# IoT_Greenhouse_V1_0_A_-_Esp32.net
KiCad netlist of a schematic drawn in Altium Designer
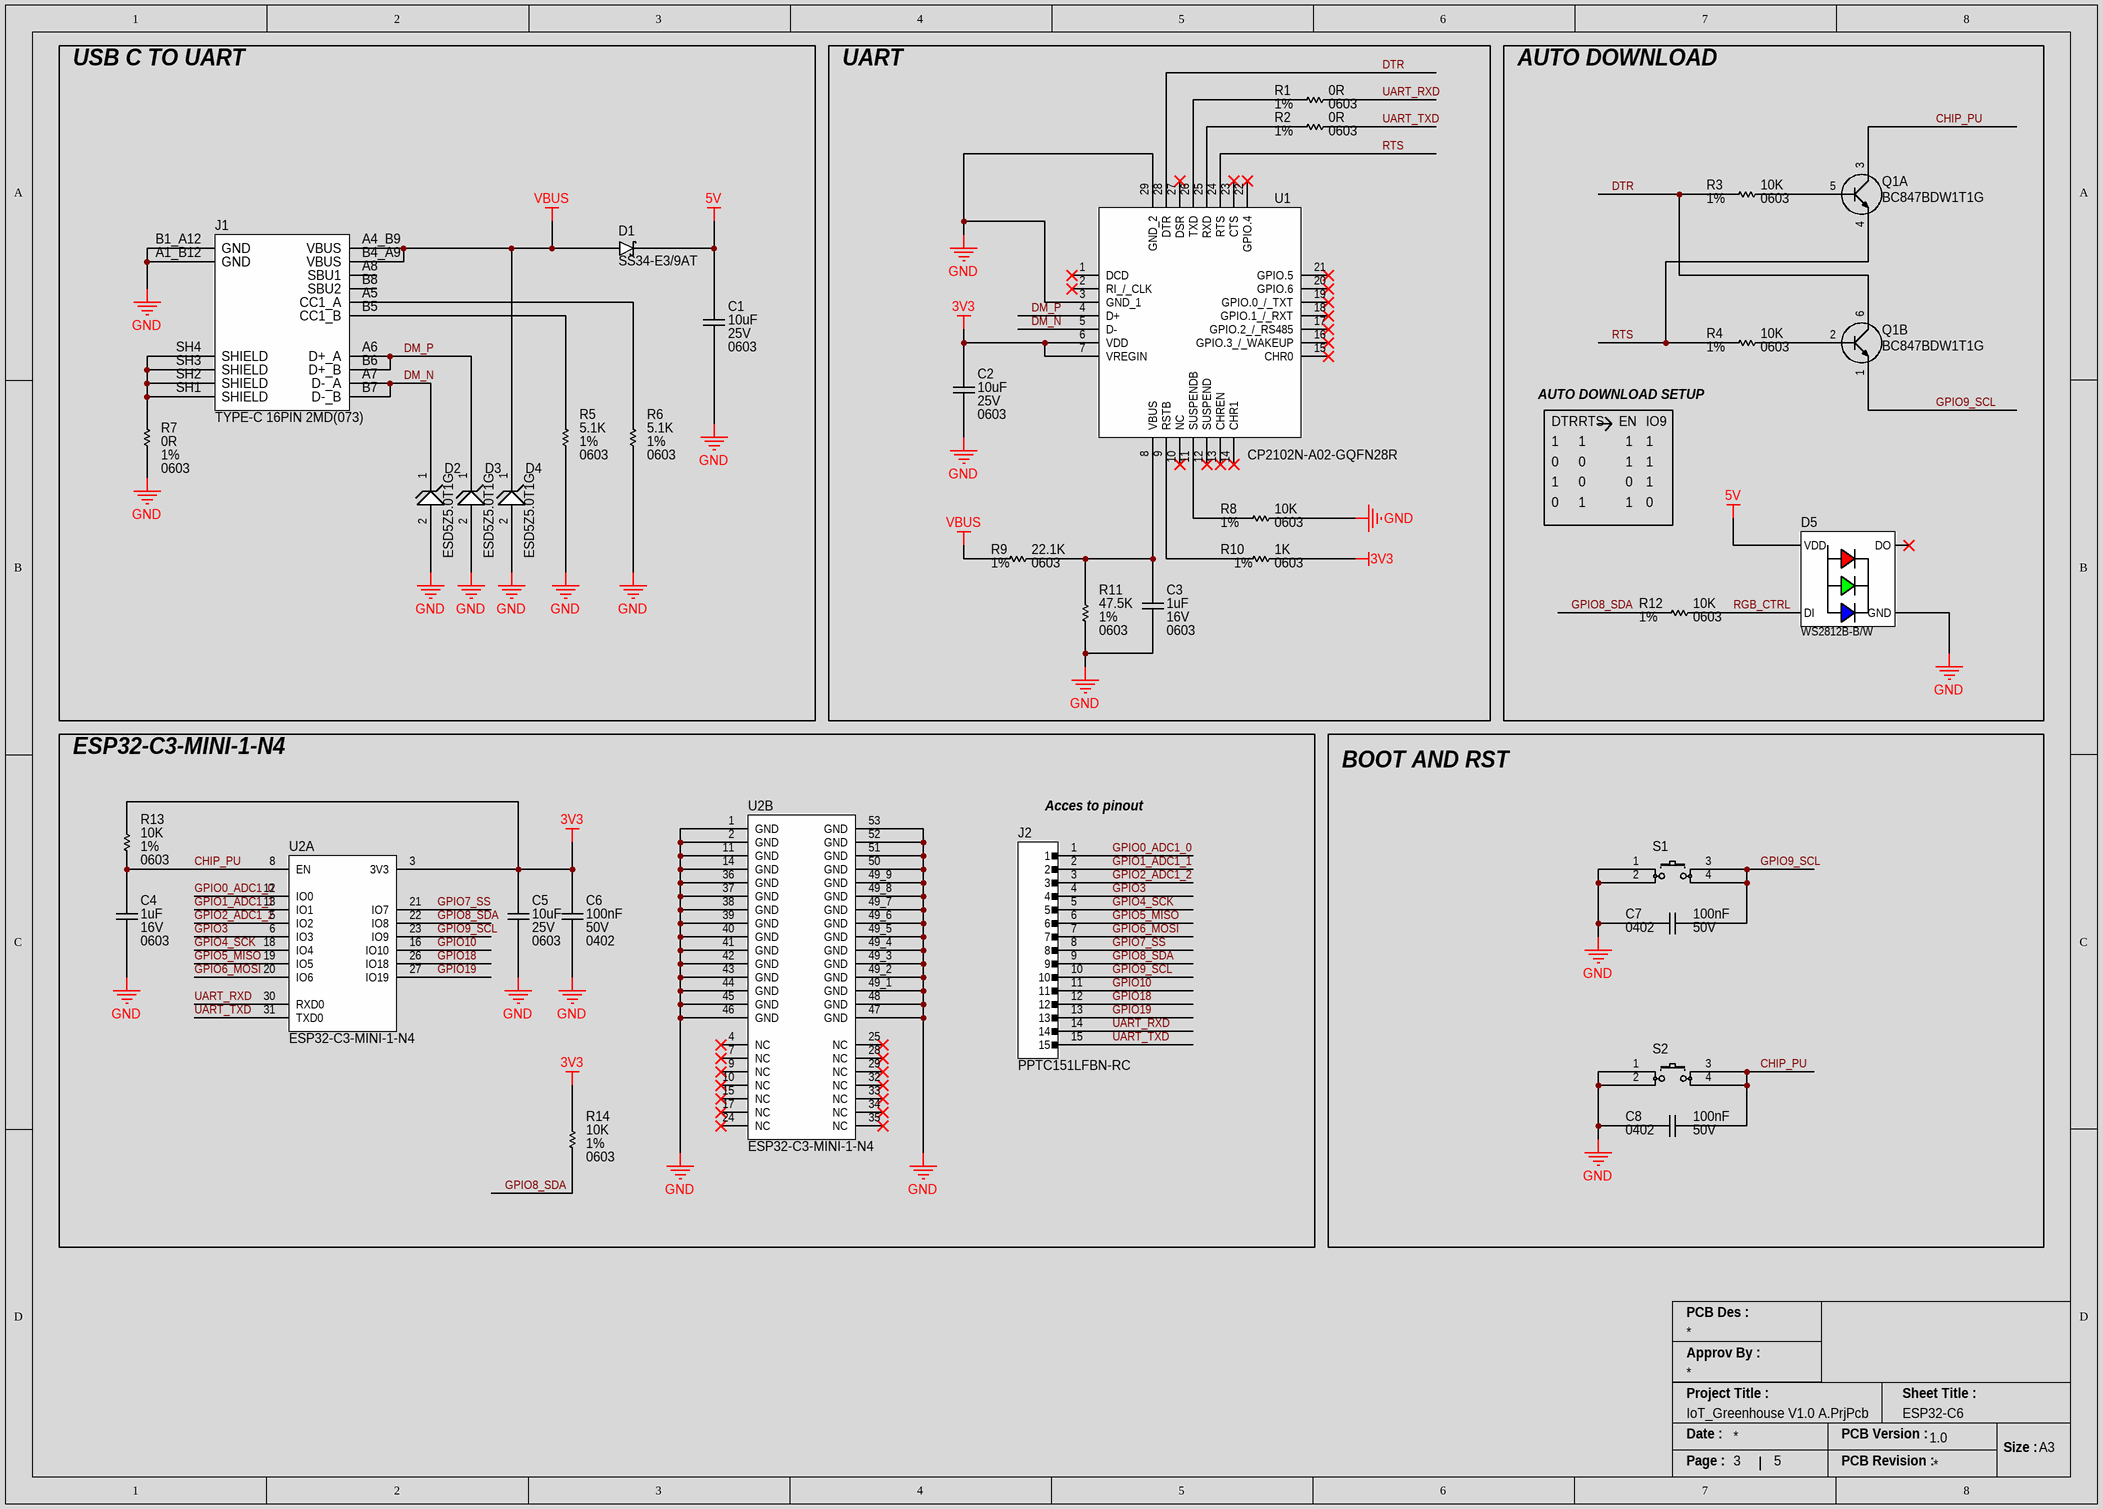
[diagram p0: IoT_Greenhouse V1.0 A - Esp32.SchDoc]

(export (version "E")
  (design (tool "Eeschema 10.0.6"))
  (components
    (comp (ref "C1")
      (value "GRM188R61E106MA73D")
      (footprint "CAP_0603_CAPC1608X08N")
      (description "Multilayer Ceramic Capacitor, 10 uF, 25 V, ± 20%, X5R, 0603 [1608 Metric]")
      (fields
        (field (name "MANUFACTURER") "Murata")
        (field (name "TOLERANCE") "20%")
        (field (name "CASE/PACKAGE") "0603")
        (field (name "CAPACITANCE") "10uF")
        (field (name "VOLTAGE RATING") "25V")
      )
      (libsource (lib "Electronic Devices_LIB") (part "CAP_10UF_25V_X5R_0603"))
    )
    (comp (ref "C2")
      (value "GRM188R61E106MA73D")
      (footprint "CAP_0603_CAPC1608X08N")
      (description "Multilayer Ceramic Capacitor, 10 uF, 25 V, ± 20%, X5R, 0603 [1608 Metric]")
      (fields
        (field (name "MANUFACTURER") "Murata")
        (field (name "TOLERANCE") "20%")
        (field (name "CASE/PACKAGE") "0603")
        (field (name "CAPACITANCE") "10uF")
        (field (name "VOLTAGE RATING") "25V")
      )
      (libsource (lib "Electronic Devices_LIB") (part "CAP_10UF_25V_X5R_0603"))
    )
    (comp (ref "C3")
      (value "CL10A105KO8NNNC")
      (footprint "CAP_0603_CAPC1608X08N")
      (description "CAP CER 1UF 16V X5R 0603")
      (fields
        (field (name "MANUFACTURER") "Samsung")
        (field (name "TOLERANCE") "10%")
        (field (name "VOLTAGE RATING") "16V")
        (field (name "CAPACITANCE") "1uF")
        (field (name "CASE/PACKAGE") "0603")
      )
      (libsource (lib "Electronic Devices_LIB") (part "CAP_1UF_16V_X5R_0603"))
    )
    (comp (ref "C4")
      (value "CL10A105KO8NNNC")
      (footprint "CAP_0603_CAPC1608X08N")
      (description "CAP CER 1UF 16V X5R 0603")
      (fields
        (field (name "MANUFACTURER") "Samsung")
        (field (name "TOLERANCE") "10%")
        (field (name "VOLTAGE RATING") "16V")
        (field (name "CAPACITANCE") "1uF")
        (field (name "CASE/PACKAGE") "0603")
      )
      (libsource (lib "Electronic Devices_LIB") (part "CAP_1UF_16V_X5R_0603"))
    )
    (comp (ref "C5")
      (value "GRM188R61E106MA73D")
      (footprint "CAP_0603_CAPC1608X08N")
      (description "Multilayer Ceramic Capacitor, 10 uF, 25 V, ± 20%, X5R, 0603 [1608 Metric]")
      (fields
        (field (name "MANUFACTURER") "Murata")
        (field (name "TOLERANCE") "20%")
        (field (name "CASE/PACKAGE") "0603")
        (field (name "CAPACITANCE") "10uF")
        (field (name "VOLTAGE RATING") "25V")
      )
      (libsource (lib "Electronic Devices_LIB") (part "CAP_10UF_25V_X5R_0603"))
    )
    (comp (ref "C6")
      (value "GRM155R71H104KE14D")
      (footprint "CAP_0402_CAPC1005X05N")
      (description "Multilayer Ceramic Capacitor, 0.1 uF, 16 V, ± 10%, X7R, 0402 [1005 Metric]")
      (fields
        (field (name "MANUFACTURER") "Murata")
        (field (name "TOLERANCE") "10%")
        (field (name "VOLTAGE RATING") "50V")
        (field (name "CAPACITANCE") "100nF")
        (field (name "CASE/PACKAGE") "0402")
      )
      (libsource (lib "Electronic Devices_LIB") (part "CAP_100NF_50V_X7R_0402"))
    )
    (comp (ref "C7")
      (value "GRM155R71H104KE14D")
      (footprint "CAP_0402_CAPC1005X05N")
      (description "Multilayer Ceramic Capacitor, 0.1 uF, 16 V, ± 10%, X7R, 0402 [1005 Metric]")
      (fields
        (field (name "MANUFACTURER") "Murata")
        (field (name "TOLERANCE") "10%")
        (field (name "VOLTAGE RATING") "50V")
        (field (name "CAPACITANCE") "100nF")
        (field (name "CASE/PACKAGE") "0402")
      )
      (libsource (lib "Electronic Devices_LIB") (part "CAP_100NF_50V_X7R_0402"))
    )
    (comp (ref "C8")
      (value "GRM155R71H104KE14D")
      (footprint "CAP_0402_CAPC1005X05N")
      (description "Multilayer Ceramic Capacitor, 0.1 uF, 16 V, ± 10%, X7R, 0402 [1005 Metric]")
      (fields
        (field (name "MANUFACTURER") "Murata")
        (field (name "TOLERANCE") "10%")
        (field (name "VOLTAGE RATING") "50V")
        (field (name "CAPACITANCE") "100nF")
        (field (name "CASE/PACKAGE") "0402")
      )
      (libsource (lib "Electronic Devices_LIB") (part "CAP_100NF_50V_X7R_0402"))
    )
    (comp (ref "D1")
      (value "SS34-E3/9AT")
      (footprint "DIO_Vishay_SMC_MFG")
      (description "Rectifier Diode, schottky, 40V V(Rrm), do-214Ab / Smc")
      (fields (field (name "MANUFACTURER") "Vishay Semiconductors"))
      (libsource (lib "Electronic Devices_LIB") (part "DIO_SCTKY_40V_3A"))
    )
    (comp (ref "D2")
      (value "ESD5Z5.0T1G")
      (footprint "SOD523_SODFL1608X70N")
      (description "ESD5Z Series 6.2 V 80 pF 5 Vrwm TVS and ESD Protection Diodes - SOD-523")
      (fields (field (name "MANUFACTURER") "ON Semiconductor"))
      (libsource (lib "Electronic Devices_LIB") (part "DIO_TVS_5V_ESD5Z5.0T1G"))
    )
    (comp (ref "D3")
      (value "ESD5Z5.0T1G")
      (footprint "SOD523_SODFL1608X70N")
      (description "ESD5Z Series 6.2 V 80 pF 5 Vrwm TVS and ESD Protection Diodes - SOD-523")
      (fields (field (name "MANUFACTURER") "ON Semiconductor"))
      (libsource (lib "Electronic Devices_LIB") (part "DIO_TVS_5V_ESD5Z5.0T1G"))
    )
    (comp (ref "D4")
      (value "ESD5Z5.0T1G")
      (footprint "SOD523_SODFL1608X70N")
      (description "ESD5Z Series 6.2 V 80 pF 5 Vrwm TVS and ESD Protection Diodes - SOD-523")
      (fields (field (name "MANUFACTURER") "ON Semiconductor"))
      (libsource (lib "Electronic Devices_LIB") (part "DIO_TVS_5V_ESD5Z5.0T1G"))
    )
    (comp (ref "D5")
      (value "WS2812B-B/W")
      (footprint "LED_RGB_3528_ XL-3528RGBW-WS2812B")
      (description "-25℃~+80℃ Positive post RGB 120° SMD3528-4P Light Emitting Diodes (LED) ROHS")
      (fields (field (name "MANUFACTURER") "XINGLIGHT") (field (name "MANUFACTURER PART NUMBER") "3528"))
      (libsource (lib "Electronic Devices_LIB") (part "LED_DIO_RGB_XL-3528RGBW-WS2812B"))
    )
    (comp (ref "J1")
      (value "TYPE-C 16PIN 2MD(073)")
      (footprint "CONN_USB_C_16P")
      (description "5A 1 Surface Mount 16P Female -25℃~+85℃ Type-C SMD USB Connectors ROHS")
      (fields (field (name "MANUFACTURER") "SHOU HAN"))
      (libsource (lib "Electronic Devices_LIB") (part "CONN_USB_TYPEC_2.0_16P_TYPE-C 16PIN 2MD(073)"))
    )
    (comp (ref "J2")
      (value "PPTC151LFBN-RC")
      (footprint "HEADER_FEM_RHDR15W85P0X254_1X15_3708X254X850P")
      (description "CONN HEADER FEMALE 15POS.1 TIN")
      (fields (field (name "MANUFACTURER") "Sullins"))
      (libsource (lib "Electronic Devices_LIB") (part "CONN_HEADER_FEMALE_15P_2.54mm"))
    )
    (comp (ref "Q1")
      (value "BC847BDW1T1G")
      (footprint "TRANS_BJT_SOT65P210X110-6N")
      (description "ON Semi BC847BDW1T1G Dual NPN Bipolar Transistor; 0.1 A; 45 V; 6-Pin SC-88")
      (fields (field (name "MANUFACTURER") "ON Semiconductor"))
      (libsource (lib "Electronic Devices_LIB") (part "TRANS_BIPOLAR_NPN_BC847BDW1T1G"))
    )
    (comp (ref "R1")
      (value "RC0603FR-070RL")
      (footprint "RES_0603_RESC1608X04N")
      (description "RC Series 0603 0.1 W 0 Ohm Jumper Surface Mount Thick Film Chip Resistor")
      (fields
        (field (name "MANUFACTURER") "Yageo")
        (field (name "TOLERANCE") "1%")
        (field (name "RESISTANCE") "0R")
        (field (name "CASE CODE (IMPERIAL)") "0603")
      )
      (libsource (lib "Electronic Devices_LIB") (part "RES_0R_1%_100mW_0603"))
    )
    (comp (ref "R2")
      (value "RC0603FR-070RL")
      (footprint "RES_0603_RESC1608X04N")
      (description "RC Series 0603 0.1 W 0 Ohm Jumper Surface Mount Thick Film Chip Resistor")
      (fields
        (field (name "MANUFACTURER") "Yageo")
        (field (name "TOLERANCE") "1%")
        (field (name "RESISTANCE") "0R")
        (field (name "CASE CODE (IMPERIAL)") "0603")
      )
      (libsource (lib "Electronic Devices_LIB") (part "RES_0R_1%_100mW_0603"))
    )
    (comp (ref "R3")
      (value "AC0603FR-1010KL")
      (footprint "RES_0603_RESC1608X04N")
      (description "Chip Resistor Automotive Grade Thick Film 0603 10kOhm 1% Paper T/R")
      (fields
        (field (name "MANUFACTURER") "Yageo")
        (field (name "RESISTANCE") "10K")
        (field (name "TOLERANCE") "1%")
        (field (name "CASE/PACKAGE") "0603")
      )
      (libsource (lib "Electronic Devices_LIB") (part "RES_10K_1%_100mW_0603"))
    )
    (comp (ref "R4")
      (value "AC0603FR-1010KL")
      (footprint "RES_0603_RESC1608X04N")
      (description "Chip Resistor Automotive Grade Thick Film 0603 10kOhm 1% Paper T/R")
      (fields
        (field (name "MANUFACTURER") "Yageo")
        (field (name "RESISTANCE") "10K")
        (field (name "TOLERANCE") "1%")
        (field (name "CASE/PACKAGE") "0603")
      )
      (libsource (lib "Electronic Devices_LIB") (part "RES_10K_1%_100mW_0603"))
    )
    (comp (ref "R5")
      (value "RC0603FR-075K1L")
      (footprint "RES_0603_RESC1608X04N")
      (description "SMD Chip Resistor, 5.1 kOhm, ± 1%, 100 mW, 0603 [1608 Metric], Thick Film, General Purpose")
      (fields
        (field (name "MANUFACTURER") "Yageo")
        (field (name "TOLERANCE") "1%")
        (field (name "RESISTANCE") "5.1K")
        (field (name "CASE/PACKAGE") "0603")
      )
      (libsource (lib "Electronic Devices_LIB") (part "RES_5.1K_1%_100mW_0603"))
    )
    (comp (ref "R6")
      (value "RC0603FR-075K1L")
      (footprint "RES_0603_RESC1608X04N")
      (description "SMD Chip Resistor, 5.1 kOhm, ± 1%, 100 mW, 0603 [1608 Metric], Thick Film, General Purpose")
      (fields
        (field (name "MANUFACTURER") "Yageo")
        (field (name "TOLERANCE") "1%")
        (field (name "RESISTANCE") "5.1K")
        (field (name "CASE/PACKAGE") "0603")
      )
      (libsource (lib "Electronic Devices_LIB") (part "RES_5.1K_1%_100mW_0603"))
    )
    (comp (ref "R7")
      (value "RC0603FR-070RL")
      (footprint "RES_0603_RESC1608X04N")
      (description "RC Series 0603 0.1 W 0 Ohm Jumper Surface Mount Thick Film Chip Resistor")
      (fields
        (field (name "MANUFACTURER") "Yageo")
        (field (name "TOLERANCE") "1%")
        (field (name "RESISTANCE") "0R")
        (field (name "CASE CODE (IMPERIAL)") "0603")
      )
      (libsource (lib "Electronic Devices_LIB") (part "RES_0R_1%_100mW_0603"))
    )
    (comp (ref "R8")
      (value "AC0603FR-1010KL")
      (footprint "RES_0603_RESC1608X04N")
      (description "Chip Resistor Automotive Grade Thick Film 0603 10kOhm 1% Paper T/R")
      (fields
        (field (name "MANUFACTURER") "Yageo")
        (field (name "RESISTANCE") "10K")
        (field (name "TOLERANCE") "1%")
        (field (name "CASE/PACKAGE") "0603")
      )
      (libsource (lib "Electronic Devices_LIB") (part "RES_10K_1%_100mW_0603"))
    )
    (comp (ref "R9")
      (value "RC0603FR-0722K1L")
      (footprint "RES_0603_RESC1608X04N")
      (description "SMD Chip Resistor, 22.1 kOhm, ± 1%, 100 mW, 0603 [1608 Metric], Thick Film, General Purpose")
      (fields
        (field (name "MANUFACTURER") "Yageo")
        (field (name "RESISTANCE") "22.1K")
        (field (name "TOLERANCE") "1%")
        (field (name "CASE/PACKAGE") "0603")
      )
      (libsource (lib "Electronic Devices_LIB") (part "RES_22.1K_1%_100mW_0603"))
    )
    (comp (ref "R10")
      (value "AC0603FR-101KL")
      (footprint "RES_0603_RESC1608X04N")
      (description "Chip Resistor Automotive Grade Thick Film 0603 1kOhm 1% Paper T/R")
      (fields
        (field (name "MANUFACTURER") "Yageo")
        (field (name "RESISTANCE") "1K")
        (field (name "TOLERANCE") "1%")
        (field (name "CASE/PACKAGE") "0603")
      )
      (libsource (lib "Electronic Devices_LIB") (part "RES_1K_1%_100mW_0603"))
    )
    (comp (ref "R11")
      (value "AC0603FR-0747K5L")
      (footprint "RES_0603_RESC1608X04N")
      (description "SMD Chip Resistor, 47.5 kOhm, ± 1%, 100 mW, 0603 [1608 Metric], Thick Film, General Purpose")
      (fields
        (field (name "MANUFACTURER") "Yageo")
        (field (name "TOLERANCE") "1%")
        (field (name "RESISTANCE") "47.5K")
        (field (name "CASE/PACKAGE") "0603")
      )
      (libsource (lib "Electronic Devices_LIB") (part "RES_47.5K_1%_100mW_0603"))
    )
    (comp (ref "R12")
      (value "AC0603FR-1010KL")
      (footprint "RES_0603_RESC1608X04N")
      (description "Chip Resistor Automotive Grade Thick Film 0603 10kOhm 1% Paper T/R")
      (fields
        (field (name "MANUFACTURER") "Yageo")
        (field (name "RESISTANCE") "10K")
        (field (name "TOLERANCE") "1%")
        (field (name "CASE/PACKAGE") "0603")
      )
      (libsource (lib "Electronic Devices_LIB") (part "RES_10K_1%_100mW_0603"))
    )
    (comp (ref "R13")
      (value "AC0603FR-1010KL")
      (footprint "RES_0603_RESC1608X04N")
      (description "Chip Resistor Automotive Grade Thick Film 0603 10kOhm 1% Paper T/R")
      (fields
        (field (name "MANUFACTURER") "Yageo")
        (field (name "RESISTANCE") "10K")
        (field (name "TOLERANCE") "1%")
        (field (name "CASE/PACKAGE") "0603")
      )
      (libsource (lib "Electronic Devices_LIB") (part "RES_10K_1%_100mW_0603"))
    )
    (comp (ref "R14")
      (value "AC0603FR-1010KL")
      (footprint "RES_0603_RESC1608X04N")
      (description "Chip Resistor Automotive Grade Thick Film 0603 10kOhm 1% Paper T/R")
      (fields
        (field (name "MANUFACTURER") "Yageo")
        (field (name "RESISTANCE") "10K")
        (field (name "TOLERANCE") "1%")
        (field (name "CASE/PACKAGE") "0603")
      )
      (libsource (lib "Electronic Devices_LIB") (part "RES_10K_1%_100mW_0603"))
    )
    (comp (ref "S1")
      (value "PTS526SK15SMTR2LFS")
      (footprint "SWT_NO_PTS526SK15SMTR2LFS")
      (description "Switch Tactile N.O. SPST Round Button Gull Wing 0.05A 12VDC 200000Cycles 2.55N SMD T/R")
      (fields (field (name "MANUFACTURER") "ITT C&K"))
      (libsource (lib "Electronic Devices_LIB") (part "SWITCH_NO_SPST_0.05A"))
    )
    (comp (ref "S2")
      (value "PTS526SK15SMTR2LFS")
      (footprint "SWT_NO_PTS526SK15SMTR2LFS")
      (description "Switch Tactile N.O. SPST Round Button Gull Wing 0.05A 12VDC 200000Cycles 2.55N SMD T/R")
      (fields (field (name "MANUFACTURER") "ITT C&K"))
      (libsource (lib "Electronic Devices_LIB") (part "SWITCH_NO_SPST_0.05A"))
    )
    (comp (ref "U1")
      (value "CP2102N-A02-GQFN28R")
      (footprint "IC_BRIDGE_UART_QFN50P500X500X80-29N-D")
      (description "Full Speed USB to UART Bridge USB 2.0 3.3V T/R Automotive 28-Pin QFN EP")
      (fields (field (name "MANUFACTURER") "Silicon Labs"))
      (libsource (lib "Electronic Devices_LIB") (part "IC_BRIDGE_UART_CP2102N-A02-GQFN28R"))
    )
    (comp (ref "U2")
      (value "ESP32-C3-MINI-1-N4")
      (footprint "XCVR_ESP32-C3-MINI-1-N4")
      (description "Multiprotocol Modules SMD module, ESP32-C3FN4, PCB antenna, -40 C +85 C")
      (fields (field (name "MANUFACTURER") "Espressif Systems"))
      (libsource (lib "Electronic Devices_LIB") (part "IC_MODULE_ESP32-C3-MINI-1-N4"))
    )
  )
  (nets
    (net (code "1") (name "/CHIP_PU") (class "Default")
      (node (ref "C4") (pin "2") (pinfunction "2_2") (pintype "passive"))
      (node (ref "C8") (pin "1") (pinfunction "1_1") (pintype "passive"))
      (node (ref "Q1") (pin "3") (pinfunction "COLLECTOR_1_3") (pintype "passive"))
      (node (ref "R13") (pin "2") (pinfunction "2_2") (pintype "passive"))
      (node (ref "S2") (pin "3") (pinfunction "NO1_3") (pintype "passive"))
      (node (ref "S2") (pin "4") (pinfunction "NO2_4") (pintype "passive"))
      (node (ref "U2") (pin "8") (pinfunction "EN_8") (pintype "passive"))
    )
    (net (code "2") (name "/DM_N") (class "Default")
      (node (ref "D2") (pin "1") (pinfunction "K_1") (pintype "passive"))
      (node (ref "J1") (pin "A7") (pinfunction "D-_A_A7") (pintype "passive"))
      (node (ref "J1") (pin "B7") (pinfunction "D-_B_B7") (pintype "passive"))
      (node (ref "U1") (pin "5") (pinfunction "D-_5") (pintype "passive"))
    )
    (net (code "3") (name "/DM_P") (class "Default")
      (node (ref "D3") (pin "1") (pinfunction "K_1") (pintype "passive"))
      (node (ref "J1") (pin "A6") (pinfunction "D+_A_A6") (pintype "passive"))
      (node (ref "J1") (pin "B6") (pinfunction "D+_B_B6") (pintype "passive"))
      (node (ref "U1") (pin "4") (pinfunction "D+_4") (pintype "passive"))
    )
    (net (code "4") (name "/DTR") (class "Default")
      (node (ref "Q1") (pin "6") (pinfunction "COLLECTOR_2_6") (pintype "passive"))
      (node (ref "R3") (pin "2") (pinfunction "2_2") (pintype "passive"))
      (node (ref "U1") (pin "28") (pinfunction "DTR_28") (pintype "passive"))
    )
    (net (code "5") (name "/GPIO0_ADC1_0") (class "Default")
      (node (ref "J2") (pin "1") (pinfunction "1_1") (pintype "passive"))
      (node (ref "U2") (pin "12") (pinfunction "IO0_12") (pintype "passive"))
    )
    (net (code "6") (name "/GPIO1_ADC1_1") (class "Default")
      (node (ref "J2") (pin "2") (pinfunction "2_2") (pintype "passive"))
      (node (ref "U2") (pin "13") (pinfunction "IO1_13") (pintype "passive"))
    )
    (net (code "7") (name "/GPIO2_ADC1_2") (class "Default")
      (node (ref "J2") (pin "3") (pinfunction "3_3") (pintype "passive"))
      (node (ref "U2") (pin "5") (pinfunction "IO2_5") (pintype "passive"))
    )
    (net (code "8") (name "/GPIO3") (class "Default")
      (node (ref "J2") (pin "4") (pinfunction "4_4") (pintype "passive"))
      (node (ref "U2") (pin "6") (pinfunction "IO3_6") (pintype "passive"))
    )
    (net (code "9") (name "/GPIO4_SCK") (class "Default")
      (node (ref "J2") (pin "5") (pinfunction "5_5") (pintype "passive"))
      (node (ref "U2") (pin "18") (pinfunction "IO4_18") (pintype "passive"))
    )
    (net (code "10") (name "/GPIO5_MISO") (class "Default")
      (node (ref "J2") (pin "6") (pinfunction "6_6") (pintype "passive"))
      (node (ref "U2") (pin "19") (pinfunction "IO5_19") (pintype "passive"))
    )
    (net (code "11") (name "/GPIO6_MOSI") (class "Default")
      (node (ref "J2") (pin "7") (pinfunction "7_7") (pintype "passive"))
      (node (ref "U2") (pin "20") (pinfunction "IO6_20") (pintype "passive"))
    )
    (net (code "12") (name "/GPIO7_SS") (class "Default")
      (node (ref "J2") (pin "8") (pinfunction "8_8") (pintype "passive"))
      (node (ref "U2") (pin "21") (pinfunction "IO7_21") (pintype "passive"))
    )
    (net (code "13") (name "/GPIO8_SDA") (class "Default")
      (node (ref "J2") (pin "9") (pinfunction "9_9") (pintype "passive"))
      (node (ref "R12") (pin "2") (pinfunction "2_2") (pintype "passive"))
      (node (ref "R14") (pin "2") (pinfunction "2_2") (pintype "passive"))
      (node (ref "U2") (pin "22") (pinfunction "IO8_22") (pintype "passive"))
    )
    (net (code "14") (name "/GPIO9_SCL") (class "Default")
      (node (ref "C7") (pin "1") (pinfunction "1_1") (pintype "passive"))
      (node (ref "J2") (pin "10") (pinfunction "10_10") (pintype "passive"))
      (node (ref "Q1") (pin "1") (pinfunction "EMITTER_2_1") (pintype "passive"))
      (node (ref "S1") (pin "3") (pinfunction "NO1_3") (pintype "passive"))
      (node (ref "S1") (pin "4") (pinfunction "NO2_4") (pintype "passive"))
      (node (ref "U2") (pin "23") (pinfunction "IO9_23") (pintype "passive"))
    )
    (net (code "15") (name "/GPIO10") (class "Default")
      (node (ref "J2") (pin "11") (pinfunction "11_11") (pintype "passive"))
      (node (ref "U2") (pin "16") (pinfunction "IO10_16") (pintype "passive"))
    )
    (net (code "16") (name "/GPIO18") (class "Default")
      (node (ref "J2") (pin "12") (pinfunction "12_12") (pintype "passive"))
      (node (ref "U2") (pin "26") (pinfunction "IO18_26") (pintype "passive"))
    )
    (net (code "17") (name "/GPIO19") (class "Default")
      (node (ref "J2") (pin "13") (pinfunction "13_13") (pintype "passive"))
      (node (ref "U2") (pin "27") (pinfunction "IO19_27") (pintype "passive"))
    )
    (net (code "18") (name "/RGB_CTRL") (class "Default")
      (node (ref "D5") (pin "2") (pinfunction "DI_2") (pintype "passive"))
      (node (ref "R12") (pin "1") (pinfunction "1_1") (pintype "passive"))
    )
    (net (code "19") (name "/RTS") (class "Default")
      (node (ref "Q1") (pin "4") (pinfunction "EMITTER_1_4") (pintype "passive"))
      (node (ref "R4") (pin "2") (pinfunction "2_2") (pintype "passive"))
      (node (ref "U1") (pin "24") (pinfunction "RTS_24") (pintype "passive"))
    )
    (net (code "20") (name "/UART_RXD") (class "Default")
      (node (ref "J2") (pin "14") (pinfunction "14_14") (pintype "passive"))
      (node (ref "R1") (pin "1") (pinfunction "1_1") (pintype "passive"))
      (node (ref "U2") (pin "30") (pinfunction "RXD0_30") (pintype "passive"))
    )
    (net (code "21") (name "/UART_TXD") (class "Default")
      (node (ref "J2") (pin "15") (pinfunction "15_15") (pintype "passive"))
      (node (ref "R2") (pin "1") (pinfunction "1_1") (pintype "passive"))
      (node (ref "U2") (pin "31") (pinfunction "TXD0_31") (pintype "passive"))
    )
    (net (code "22") (name "3V3") (class "Default")
      (node (ref "C2") (pin "2") (pinfunction "2_2") (pintype "passive"))
      (node (ref "C5") (pin "2") (pinfunction "2_2") (pintype "passive"))
      (node (ref "C6") (pin "2") (pinfunction "2_2") (pintype "passive"))
      (node (ref "R10") (pin "2") (pinfunction "2_2") (pintype "passive"))
      (node (ref "R13") (pin "1") (pinfunction "1_1") (pintype "passive"))
      (node (ref "R14") (pin "1") (pinfunction "1_1") (pintype "passive"))
      (node (ref "U1") (pin "6") (pinfunction "VDD_6") (pintype "passive"))
      (node (ref "U1") (pin "7") (pinfunction "VREGIN_7") (pintype "passive"))
      (node (ref "U2") (pin "3") (pinfunction "3V3_3") (pintype "passive"))
    )
    (net (code "23") (name "5V") (class "Default")
      (node (ref "C1") (pin "2") (pinfunction "2_2") (pintype "passive"))
      (node (ref "D1") (pin "1") (pinfunction "K_1") (pintype "passive"))
      (node (ref "D5") (pin "3") (pinfunction "VDD_3") (pintype "power_in"))
    )
    (net (code "24") (name "GND") (class "Default")
      (node (ref "C1") (pin "1") (pinfunction "1_1") (pintype "passive"))
      (node (ref "C2") (pin "1") (pinfunction "1_1") (pintype "passive"))
      (node (ref "C3") (pin "1") (pinfunction "1_1") (pintype "passive"))
      (node (ref "C4") (pin "1") (pinfunction "1_1") (pintype "passive"))
      (node (ref "C5") (pin "1") (pinfunction "1_1") (pintype "passive"))
      (node (ref "C6") (pin "1") (pinfunction "1_1") (pintype "passive"))
      (node (ref "C7") (pin "2") (pinfunction "2_2") (pintype "passive"))
      (node (ref "C8") (pin "2") (pinfunction "2_2") (pintype "passive"))
      (node (ref "D2") (pin "2") (pinfunction "A_2") (pintype "passive"))
      (node (ref "D3") (pin "2") (pinfunction "A_2") (pintype "passive"))
      (node (ref "D4") (pin "2") (pinfunction "A_2") (pintype "passive"))
      (node (ref "D5") (pin "1") (pinfunction "GND_1") (pintype "power_in"))
      (node (ref "J1") (pin "A1_B12") (pinfunction "GND_A1_B12") (pintype "power_in"))
      (node (ref "J1") (pin "B1_A12") (pinfunction "GND_B1_A12") (pintype "power_in"))
      (node (ref "R11") (pin "1") (pinfunction "1_1") (pintype "passive"))
      (node (ref "R5") (pin "1") (pinfunction "1_1") (pintype "passive"))
      (node (ref "R6") (pin "1") (pinfunction "1_1") (pintype "passive"))
      (node (ref "R7") (pin "1") (pinfunction "1_1") (pintype "passive"))
      (node (ref "R8") (pin "2") (pinfunction "2_2") (pintype "passive"))
      (node (ref "S1") (pin "1") (pinfunction "COM_1_1") (pintype "passive"))
      (node (ref "S1") (pin "2") (pinfunction "COM2_2") (pintype "passive"))
      (node (ref "S2") (pin "1") (pinfunction "COM_1_1") (pintype "passive"))
      (node (ref "S2") (pin "2") (pinfunction "COM2_2") (pintype "passive"))
      (node (ref "U1") (pin "29") (pinfunction "GND_2_29") (pintype "passive"))
      (node (ref "U1") (pin "3") (pinfunction "GND_1_3") (pintype "passive"))
      (node (ref "U2") (pin "1") (pinfunction "GND_1") (pintype "power_in"))
      (node (ref "U2") (pin "11") (pinfunction "GND_11") (pintype "power_in"))
      (node (ref "U2") (pin "14") (pinfunction "GND_14") (pintype "power_in"))
      (node (ref "U2") (pin "2") (pinfunction "GND_2") (pintype "power_in"))
      (node (ref "U2") (pin "36") (pinfunction "GND_36") (pintype "power_in"))
      (node (ref "U2") (pin "37") (pinfunction "GND_37") (pintype "power_in"))
      (node (ref "U2") (pin "38") (pinfunction "GND_38") (pintype "power_in"))
      (node (ref "U2") (pin "39") (pinfunction "GND_39") (pintype "power_in"))
      (node (ref "U2") (pin "40") (pinfunction "GND_40") (pintype "power_in"))
      (node (ref "U2") (pin "41") (pinfunction "GND_41") (pintype "power_in"))
      (node (ref "U2") (pin "42") (pinfunction "GND_42") (pintype "power_in"))
      (node (ref "U2") (pin "43") (pinfunction "GND_43") (pintype "power_in"))
      (node (ref "U2") (pin "44") (pinfunction "GND_44") (pintype "power_in"))
      (node (ref "U2") (pin "45") (pinfunction "GND_45") (pintype "power_in"))
      (node (ref "U2") (pin "46") (pinfunction "GND_46") (pintype "power_in"))
      (node (ref "U2") (pin "47") (pinfunction "GND_47") (pintype "power_in"))
      (node (ref "U2") (pin "48") (pinfunction "GND_48") (pintype "power_in"))
      (node (ref "U2") (pin "49_1") (pinfunction "GND_49_1") (pintype "power_in"))
      (node (ref "U2") (pin "49_2") (pinfunction "GND_49_2") (pintype "power_in"))
      (node (ref "U2") (pin "49_3") (pinfunction "GND_49_3") (pintype "power_in"))
      (node (ref "U2") (pin "49_4") (pinfunction "GND_49_4") (pintype "power_in"))
      (node (ref "U2") (pin "49_5") (pinfunction "GND_49_5") (pintype "power_in"))
      (node (ref "U2") (pin "49_6") (pinfunction "GND_49_6") (pintype "power_in"))
      (node (ref "U2") (pin "49_7") (pinfunction "GND_49_7") (pintype "power_in"))
      (node (ref "U2") (pin "49_8") (pinfunction "GND_49_8") (pintype "power_in"))
      (node (ref "U2") (pin "49_9") (pinfunction "GND_49_9") (pintype "power_in"))
      (node (ref "U2") (pin "50") (pinfunction "GND_50") (pintype "power_in"))
      (node (ref "U2") (pin "51") (pinfunction "GND_51") (pintype "power_in"))
      (node (ref "U2") (pin "52") (pinfunction "GND_52") (pintype "power_in"))
      (node (ref "U2") (pin "53") (pinfunction "GND_53") (pintype "power_in"))
    )
    (net (code "25") (name "Net-(J1-CC1_A)") (class "Default")
      (node (ref "J1") (pin "A5") (pinfunction "CC1_A_A5") (pintype "passive"))
      (node (ref "R6") (pin "2") (pinfunction "2_2") (pintype "passive"))
    )
    (net (code "26") (name "Net-(J1-CC1_B)") (class "Default")
      (node (ref "J1") (pin "B5") (pinfunction "CC1_B_B5") (pintype "passive"))
      (node (ref "R5") (pin "2") (pinfunction "2_2") (pintype "passive"))
    )
    (net (code "27") (name "Net-(J1-SHIELD-PadSH1)") (class "Default")
      (node (ref "J1") (pin "SH1") (pinfunction "SHIELD_SH1") (pintype "passive"))
      (node (ref "J1") (pin "SH2") (pinfunction "SHIELD_SH2") (pintype "passive"))
      (node (ref "J1") (pin "SH3") (pinfunction "SHIELD_SH3") (pintype "passive"))
      (node (ref "J1") (pin "SH4") (pinfunction "SHIELD_SH4") (pintype "passive"))
      (node (ref "R7") (pin "2") (pinfunction "2_2") (pintype "passive"))
    )
    (net (code "28") (name "Net-(Q1A-BASE_1)") (class "Default")
      (node (ref "Q1") (pin "5") (pinfunction "BASE_1_5") (pintype "passive"))
      (node (ref "R3") (pin "1") (pinfunction "1_1") (pintype "passive"))
    )
    (net (code "29") (name "Net-(Q1B-BASE_2)") (class "Default")
      (node (ref "Q1") (pin "2") (pinfunction "BASE_2_2") (pintype "passive"))
      (node (ref "R4") (pin "1") (pinfunction "1_1") (pintype "passive"))
    )
    (net (code "30") (name "Net-(U1-RSTB)") (class "Default")
      (node (ref "R10") (pin "1") (pinfunction "1_1") (pintype "passive"))
      (node (ref "U1") (pin "9") (pinfunction "RSTB_9") (pintype "passive"))
    )
    (net (code "31") (name "Net-(U1-RXD)") (class "Default")
      (node (ref "R2") (pin "2") (pinfunction "2_2") (pintype "passive"))
      (node (ref "U1") (pin "25") (pinfunction "RXD_25") (pintype "passive"))
    )
    (net (code "32") (name "Net-(U1-SUSPENDB)") (class "Default")
      (node (ref "R8") (pin "1") (pinfunction "1_1") (pintype "passive"))
      (node (ref "U1") (pin "11") (pinfunction "SUSPENDB_11") (pintype "passive"))
    )
    (net (code "33") (name "Net-(U1-TXD)") (class "Default")
      (node (ref "R1") (pin "2") (pinfunction "2_2") (pintype "passive"))
      (node (ref "U1") (pin "26") (pinfunction "TXD_26") (pintype "passive"))
    )
    (net (code "34") (name "Net-(U1-VBUS)") (class "Default")
      (node (ref "C3") (pin "2") (pinfunction "2_2") (pintype "passive"))
      (node (ref "R11") (pin "2") (pinfunction "2_2") (pintype "passive"))
      (node (ref "R9") (pin "2") (pinfunction "2_2") (pintype "passive"))
      (node (ref "U1") (pin "8") (pinfunction "VBUS_8") (pintype "passive"))
    )
    (net (code "35") (name "VBUS") (class "Default")
      (node (ref "D1") (pin "2") (pinfunction "A_2") (pintype "passive"))
      (node (ref "D4") (pin "1") (pinfunction "K_1") (pintype "passive"))
      (node (ref "J1") (pin "A4_B9") (pinfunction "VBUS_A4_B9") (pintype "power_in"))
      (node (ref "J1") (pin "B4_A9") (pinfunction "VBUS_B4_A9") (pintype "power_in"))
      (node (ref "R9") (pin "1") (pinfunction "1_1") (pintype "passive"))
    )
    (net (code "36") (name "unconnected-(D5-DO-Pad4)") (class "Default")
      (node (ref "D5") (pin "4") (pinfunction "DO_4") (pintype "passive+no_connect"))
    )
    (net (code "37") (name "unconnected-(J1-SBU1-PadA8)") (class "Default")
      (node (ref "J1") (pin "A8") (pinfunction "SBU1_A8") (pintype "passive"))
    )
    (net (code "38") (name "unconnected-(J1-SBU2-PadB8)") (class "Default")
      (node (ref "J1") (pin "B8") (pinfunction "SBU2_B8") (pintype "passive"))
    )
    (net (code "39") (name "unconnected-(U1-CHR0-Pad15)") (class "Default")
      (node (ref "U1") (pin "15") (pinfunction "CHR0_15") (pintype "passive+no_connect"))
    )
    (net (code "40") (name "unconnected-(U1-CHR1-Pad14)") (class "Default")
      (node (ref "U1") (pin "14") (pinfunction "CHR1_14") (pintype "passive+no_connect"))
    )
    (net (code "41") (name "unconnected-(U1-CHREN-Pad13)") (class "Default")
      (node (ref "U1") (pin "13") (pinfunction "CHREN_13") (pintype "passive+no_connect"))
    )
    (net (code "42") (name "unconnected-(U1-CTS-Pad23)") (class "Default")
      (node (ref "U1") (pin "23") (pinfunction "CTS_23") (pintype "passive+no_connect"))
    )
    (net (code "43") (name "unconnected-(U1-DCD-Pad1)") (class "Default")
      (node (ref "U1") (pin "1") (pinfunction "DCD_1") (pintype "passive+no_connect"))
    )
    (net (code "44") (name "unconnected-(U1-DSR-Pad27)") (class "Default")
      (node (ref "U1") (pin "27") (pinfunction "DSR_27") (pintype "passive+no_connect"))
    )
    (net (code "45") (name "unconnected-(U1-GPIO.0_{slash}_TXT-Pad19)") (class "Default")
      (node (ref "U1") (pin "19") (pinfunction "GPIO.0_/_TXT_19") (pintype "passive+no_connect"))
    )
    (net (code "46") (name "unconnected-(U1-GPIO.1_{slash}_RXT-Pad18)") (class "Default")
      (node (ref "U1") (pin "18") (pinfunction "GPIO.1_/_RXT_18") (pintype "passive+no_connect"))
    )
    (net (code "47") (name "unconnected-(U1-GPIO.2_{slash}_RS485-Pad17)") (class "Default")
      (node (ref "U1") (pin "17") (pinfunction "GPIO.2_/_RS485_17") (pintype "passive+no_connect"))
    )
    (net (code "48") (name "unconnected-(U1-GPIO.3_{slash}_WAKEUP-Pad16)") (class "Default")
      (node (ref "U1") (pin "16") (pinfunction "GPIO.3_/_WAKEUP_16") (pintype "passive+no_connect"))
    )
    (net (code "49") (name "unconnected-(U1-GPIO.4-Pad22)") (class "Default")
      (node (ref "U1") (pin "22") (pinfunction "GPIO.4_22") (pintype "passive+no_connect"))
    )
    (net (code "50") (name "unconnected-(U1-GPIO.5-Pad21)") (class "Default")
      (node (ref "U1") (pin "21") (pinfunction "GPIO.5_21") (pintype "passive+no_connect"))
    )
    (net (code "51") (name "unconnected-(U1-GPIO.6-Pad20)") (class "Default")
      (node (ref "U1") (pin "20") (pinfunction "GPIO.6_20") (pintype "passive+no_connect"))
    )
    (net (code "52") (name "unconnected-(U1-NC-Pad10)") (class "Default")
      (node (ref "U1") (pin "10") (pinfunction "NC_10") (pintype "passive+no_connect"))
    )
    (net (code "53") (name "unconnected-(U1-RI_{slash}_CLK-Pad2)") (class "Default")
      (node (ref "U1") (pin "2") (pinfunction "RI_/_CLK_2") (pintype "passive+no_connect"))
    )
    (net (code "54") (name "unconnected-(U1-SUSPEND-Pad12)") (class "Default")
      (node (ref "U1") (pin "12") (pinfunction "SUSPEND_12") (pintype "passive+no_connect"))
    )
    (net (code "55") (name "unconnected-(U2B-NC-Pad4)") (class "Default")
      (node (ref "U2") (pin "4") (pinfunction "NC_4") (pintype "passive+no_connect"))
    )
    (net (code "56") (name "unconnected-(U2B-NC-Pad7)") (class "Default")
      (node (ref "U2") (pin "7") (pinfunction "NC_7") (pintype "passive+no_connect"))
    )
    (net (code "57") (name "unconnected-(U2B-NC-Pad9)") (class "Default")
      (node (ref "U2") (pin "9") (pinfunction "NC_9") (pintype "passive+no_connect"))
    )
    (net (code "58") (name "unconnected-(U2B-NC-Pad10)") (class "Default")
      (node (ref "U2") (pin "10") (pinfunction "NC_10") (pintype "passive+no_connect"))
    )
    (net (code "59") (name "unconnected-(U2B-NC-Pad15)") (class "Default")
      (node (ref "U2") (pin "15") (pinfunction "NC_15") (pintype "passive+no_connect"))
    )
    (net (code "60") (name "unconnected-(U2B-NC-Pad17)") (class "Default")
      (node (ref "U2") (pin "17") (pinfunction "NC_17") (pintype "passive+no_connect"))
    )
    (net (code "61") (name "unconnected-(U2B-NC-Pad24)") (class "Default")
      (node (ref "U2") (pin "24") (pinfunction "NC_24") (pintype "passive+no_connect"))
    )
    (net (code "62") (name "unconnected-(U2B-NC-Pad25)") (class "Default")
      (node (ref "U2") (pin "25") (pinfunction "NC_25") (pintype "passive+no_connect"))
    )
    (net (code "63") (name "unconnected-(U2B-NC-Pad28)") (class "Default")
      (node (ref "U2") (pin "28") (pinfunction "NC_28") (pintype "passive+no_connect"))
    )
    (net (code "64") (name "unconnected-(U2B-NC-Pad29)") (class "Default")
      (node (ref "U2") (pin "29") (pinfunction "NC_29") (pintype "passive+no_connect"))
    )
    (net (code "65") (name "unconnected-(U2B-NC-Pad32)") (class "Default")
      (node (ref "U2") (pin "32") (pinfunction "NC_32") (pintype "passive+no_connect"))
    )
    (net (code "66") (name "unconnected-(U2B-NC-Pad33)") (class "Default")
      (node (ref "U2") (pin "33") (pinfunction "NC_33") (pintype "passive+no_connect"))
    )
    (net (code "67") (name "unconnected-(U2B-NC-Pad34)") (class "Default")
      (node (ref "U2") (pin "34") (pinfunction "NC_34") (pintype "passive+no_connect"))
    )
    (net (code "68") (name "unconnected-(U2B-NC-Pad35)") (class "Default")
      (node (ref "U2") (pin "35") (pinfunction "NC_35") (pintype "passive+no_connect"))
    )
  )
)
